# tweeq-FB_IO_V3.net
KiCad netlist of a schematic drawn in EAGLE
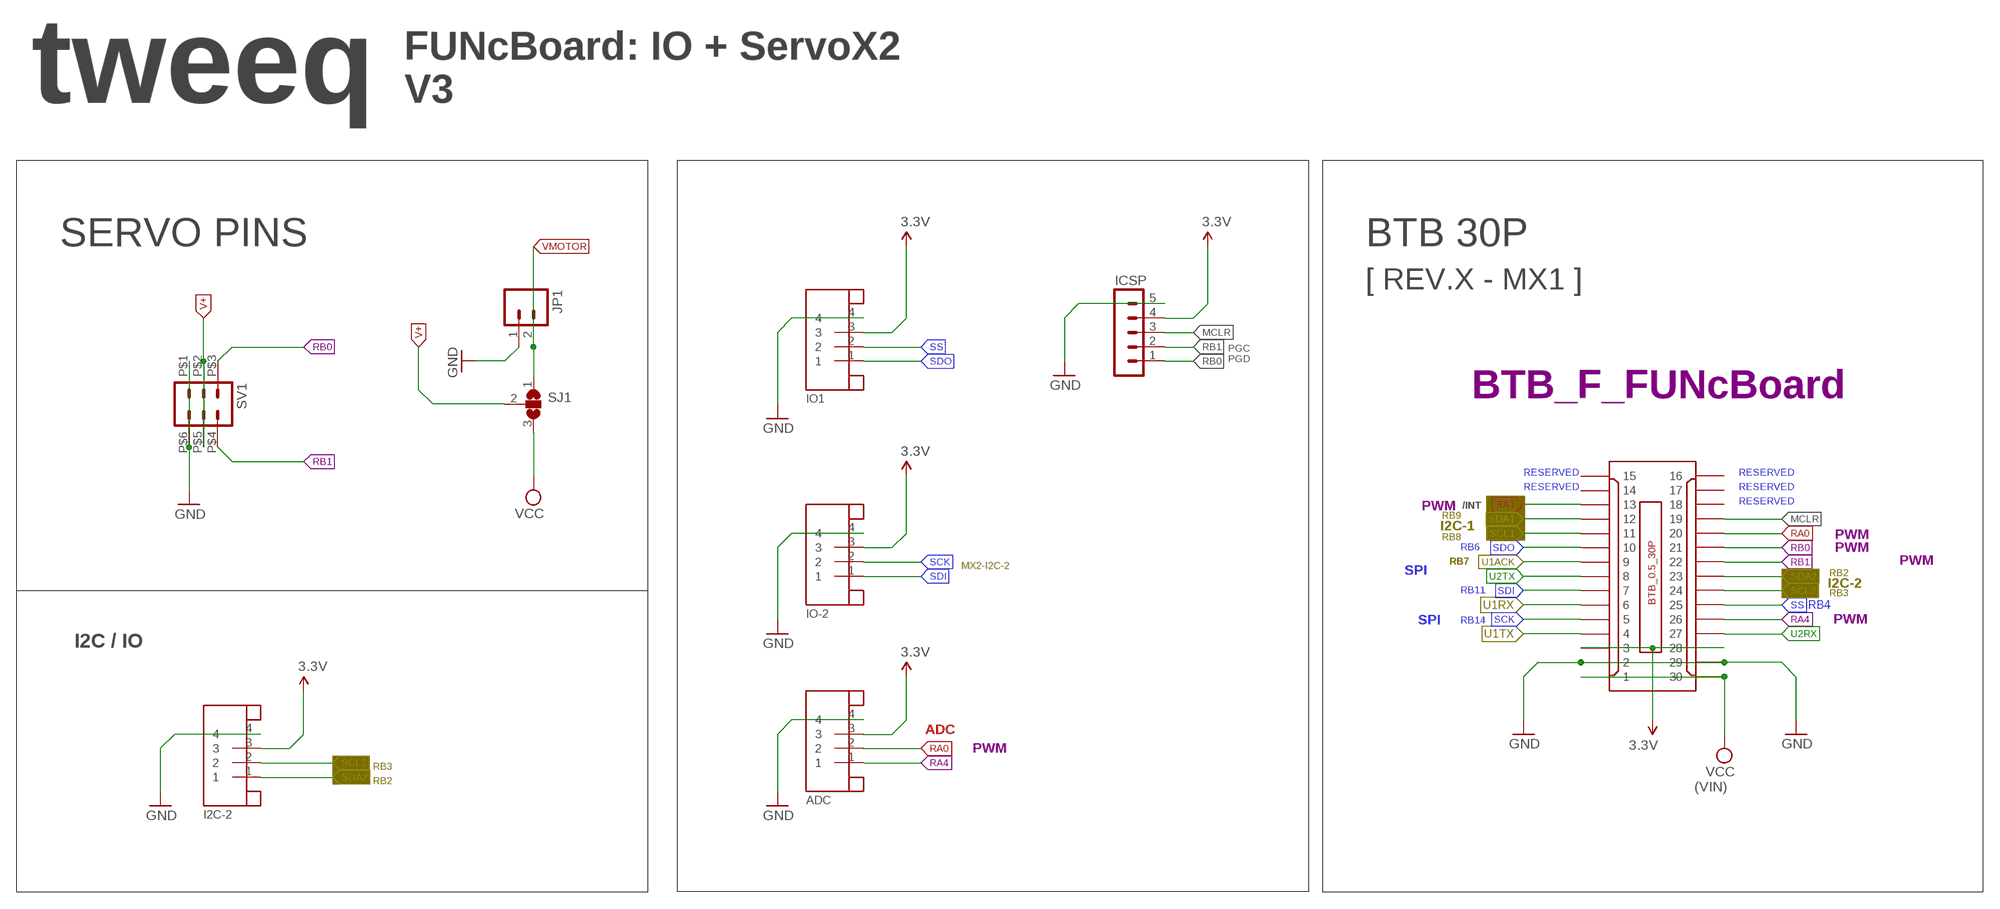
[diagram p0: schematic, sheet 1]

(export (version "E")
  (design (tool "Eeschema 10.0.6"))
  (components
    (comp (ref "ADC")
      (value "JST-4PINSH")
      (footprint "eagle-import:SH1.0-4PIN")
      (libsource (lib "eagle-import") (part "JST-4PINSH"))
    )
    (comp (ref "I2C-2")
      (value "JST-4PINSH")
      (footprint "eagle-import:SH1.0-4PIN")
      (libsource (lib "eagle-import") (part "JST-4PINSH"))
    )
    (comp (ref "ICSP")
      (value "M05-1NOSILK")
      (footprint "eagle-import:1X05_NOSILK")
      (libsource (lib "eagle-import") (part "M05-1NOSILK"))
    )
    (comp (ref "IO-2")
      (value "JST-4PINSH")
      (footprint "eagle-import:SH1.0-4PIN")
      (libsource (lib "eagle-import") (part "JST-4PINSH"))
    )
    (comp (ref "IO1")
      (value "JST-4PINSH")
      (footprint "eagle-import:SH1.0-4PIN")
      (libsource (lib "eagle-import") (part "JST-4PINSH"))
    )
    (comp (ref "JP1")
      (value "M022.54-POL-TH")
      (footprint "eagle-import:1X02_2.54POL_TH")
      (libsource (lib "eagle-import") (part "M022.54-POL-TH"))
    )
    (comp (ref "SJ1")
      (value "JUMPER_SJ2W")
      (footprint "eagle-import:JUMPER_SJ_2")
      (libsource (lib "eagle-import") (part "JUMPER_SJ2W"))
    )
    (comp (ref "SV1")
      (value "M03-2EDGE_PAD")
      (footprint "eagle-import:2X03_EDGEPAD")
      (libsource (lib "eagle-import") (part "M03-2EDGE_PAD"))
    )
    (comp (ref "U$1")
      (value "BTB_CONN_30P/F")
      (footprint "eagle-import:BTB0.5-30F-3.0G")
      (libsource (lib "eagle-import") (part "BTB_CONN_30P/F"))
    )
  )
  (nets
    (net (code "1") (name "3.3V") (class "Default")
      (node (ref "ADC") (pin "3") (pinfunction "3_3") (pintype "bidirectional"))
      (node (ref "I2C-2") (pin "3") (pinfunction "3_3") (pintype "bidirectional"))
      (node (ref "ICSP") (pin "4") (pinfunction "4_4") (pintype "passive"))
      (node (ref "IO-2") (pin "3") (pinfunction "3_3") (pintype "bidirectional"))
      (node (ref "IO1") (pin "3") (pinfunction "3_3") (pintype "bidirectional"))
      (node (ref "U$1") (pin "28") (pinfunction "28_28") (pintype "bidirectional"))
      (node (ref "U$1") (pin "3") (pinfunction "3_3") (pintype "bidirectional"))
    )
    (net (code "2") (name "GND") (class "Default")
      (node (ref "ADC") (pin "4") (pinfunction "4_4") (pintype "bidirectional"))
      (node (ref "I2C-2") (pin "4") (pinfunction "4_4") (pintype "bidirectional"))
      (node (ref "ICSP") (pin "5") (pinfunction "5_5") (pintype "passive"))
      (node (ref "IO-2") (pin "4") (pinfunction "4_4") (pintype "bidirectional"))
      (node (ref "IO1") (pin "4") (pinfunction "4_4") (pintype "bidirectional"))
      (node (ref "JP1") (pin "1") (pinfunction "1_1") (pintype "passive"))
      (node (ref "SV1") (pin "P$1") (pinfunction "1_P$1") (pintype "passive"))
      (node (ref "SV1") (pin "P$6") (pinfunction "6_P$6") (pintype "passive"))
      (node (ref "U$1") (pin "2") (pinfunction "2_2") (pintype "bidirectional"))
      (node (ref "U$1") (pin "29") (pinfunction "29_29") (pintype "bidirectional"))
    )
    (net (code "3") (name "MCLR") (class "Default")
      (node (ref "ICSP") (pin "3") (pinfunction "3_3") (pintype "passive"))
      (node (ref "U$1") (pin "19") (pinfunction "19_19") (pintype "bidirectional"))
    )
    (net (code "4") (name "RA0") (class "Default")
      (node (ref "ADC") (pin "2") (pinfunction "2_2") (pintype "bidirectional"))
      (node (ref "U$1") (pin "20") (pinfunction "20_20") (pintype "bidirectional"))
    )
    (net (code "5") (name "RA1") (class "Default")
      (node (ref "U$1") (pin "13") (pinfunction "13_13") (pintype "bidirectional"))
    )
    (net (code "6") (name "RA4") (class "Default")
      (node (ref "ADC") (pin "1") (pinfunction "1_1") (pintype "bidirectional"))
      (node (ref "U$1") (pin "26") (pinfunction "26_26") (pintype "bidirectional"))
    )
    (net (code "7") (name "RB0") (class "Default")
      (node (ref "ICSP") (pin "1") (pinfunction "1_1") (pintype "passive"))
      (node (ref "SV1") (pin "P$3") (pinfunction "3_P$3") (pintype "passive"))
      (node (ref "U$1") (pin "21") (pinfunction "21_21") (pintype "bidirectional"))
    )
    (net (code "8") (name "RB1") (class "Default")
      (node (ref "ICSP") (pin "2") (pinfunction "2_2") (pintype "passive"))
      (node (ref "SV1") (pin "P$4") (pinfunction "4_P$4") (pintype "passive"))
      (node (ref "U$1") (pin "22") (pinfunction "22_22") (pintype "bidirectional"))
    )
    (net (code "9") (name "SCK") (class "Default")
      (node (ref "IO-2") (pin "2") (pinfunction "2_2") (pintype "bidirectional"))
      (node (ref "U$1") (pin "5") (pinfunction "5_5") (pintype "bidirectional"))
    )
    (net (code "10") (name "SCL1") (class "Default")
      (node (ref "U$1") (pin "11") (pinfunction "11_11") (pintype "bidirectional"))
    )
    (net (code "11") (name "SCL2") (class "Default")
      (node (ref "I2C-2") (pin "2") (pinfunction "2_2") (pintype "bidirectional"))
      (node (ref "U$1") (pin "24") (pinfunction "24_24") (pintype "bidirectional"))
    )
    (net (code "12") (name "SDA1") (class "Default")
      (node (ref "U$1") (pin "12") (pinfunction "12_12") (pintype "bidirectional"))
    )
    (net (code "13") (name "SDA2") (class "Default")
      (node (ref "I2C-2") (pin "1") (pinfunction "1_1") (pintype "bidirectional"))
      (node (ref "U$1") (pin "23") (pinfunction "23_23") (pintype "bidirectional"))
    )
    (net (code "14") (name "SDI") (class "Default")
      (node (ref "IO-2") (pin "1") (pinfunction "1_1") (pintype "bidirectional"))
      (node (ref "U$1") (pin "7") (pinfunction "7_7") (pintype "bidirectional"))
    )
    (net (code "15") (name "SDO") (class "Default")
      (node (ref "IO1") (pin "1") (pinfunction "1_1") (pintype "bidirectional"))
      (node (ref "U$1") (pin "10") (pinfunction "10_10") (pintype "bidirectional"))
    )
    (net (code "16") (name "SS") (class "Default")
      (node (ref "IO1") (pin "2") (pinfunction "2_2") (pintype "bidirectional"))
      (node (ref "U$1") (pin "25") (pinfunction "25_25") (pintype "bidirectional"))
    )
    (net (code "17") (name "U1ACK") (class "Default")
      (node (ref "U$1") (pin "9") (pinfunction "9_9") (pintype "bidirectional"))
    )
    (net (code "18") (name "U1RX") (class "Default")
      (node (ref "U$1") (pin "6") (pinfunction "6_6") (pintype "bidirectional"))
    )
    (net (code "19") (name "U1TX") (class "Default")
      (node (ref "U$1") (pin "4") (pinfunction "4_4") (pintype "bidirectional"))
    )
    (net (code "20") (name "U2RX") (class "Default")
      (node (ref "U$1") (pin "27") (pinfunction "27_27") (pintype "bidirectional"))
    )
    (net (code "21") (name "U2TX") (class "Default")
      (node (ref "U$1") (pin "8") (pinfunction "8_8") (pintype "bidirectional"))
    )
    (net (code "22") (name "V+") (class "Default")
      (node (ref "SJ1") (pin "2") (pinfunction "2_2") (pintype "passive"))
      (node (ref "SV1") (pin "P$2") (pinfunction "2_P$2") (pintype "passive"))
      (node (ref "SV1") (pin "P$5") (pinfunction "5_P$5") (pintype "passive"))
    )
    (net (code "23") (name "VCC") (class "Default")
      (node (ref "SJ1") (pin "3") (pinfunction "3_3") (pintype "passive"))
      (node (ref "U$1") (pin "1") (pinfunction "1_1") (pintype "bidirectional"))
      (node (ref "U$1") (pin "30") (pinfunction "30_30") (pintype "bidirectional"))
    )
    (net (code "24") (name "VMOTOR") (class "Default")
      (node (ref "JP1") (pin "2") (pinfunction "2_2") (pintype "passive"))
      (node (ref "SJ1") (pin "1") (pinfunction "1_1") (pintype "passive"))
    )
    (net (code "25") (name "unconnected-(U$1-Pad14)") (class "Default")
      (node (ref "U$1") (pin "14") (pinfunction "14_14") (pintype "bidirectional"))
    )
    (net (code "26") (name "unconnected-(U$1-Pad15)") (class "Default")
      (node (ref "U$1") (pin "15") (pinfunction "15_15") (pintype "bidirectional"))
    )
    (net (code "27") (name "unconnected-(U$1-Pad16)") (class "Default")
      (node (ref "U$1") (pin "16") (pinfunction "16_16") (pintype "bidirectional"))
    )
    (net (code "28") (name "unconnected-(U$1-Pad17)") (class "Default")
      (node (ref "U$1") (pin "17") (pinfunction "17_17") (pintype "bidirectional"))
    )
    (net (code "29") (name "unconnected-(U$1-Pad18)") (class "Default")
      (node (ref "U$1") (pin "18") (pinfunction "18_18") (pintype "bidirectional"))
    )
  )
)
